# 2013_Carte_Factorisee.net
KiCad netlist of a schematic drawn in Altium Designer
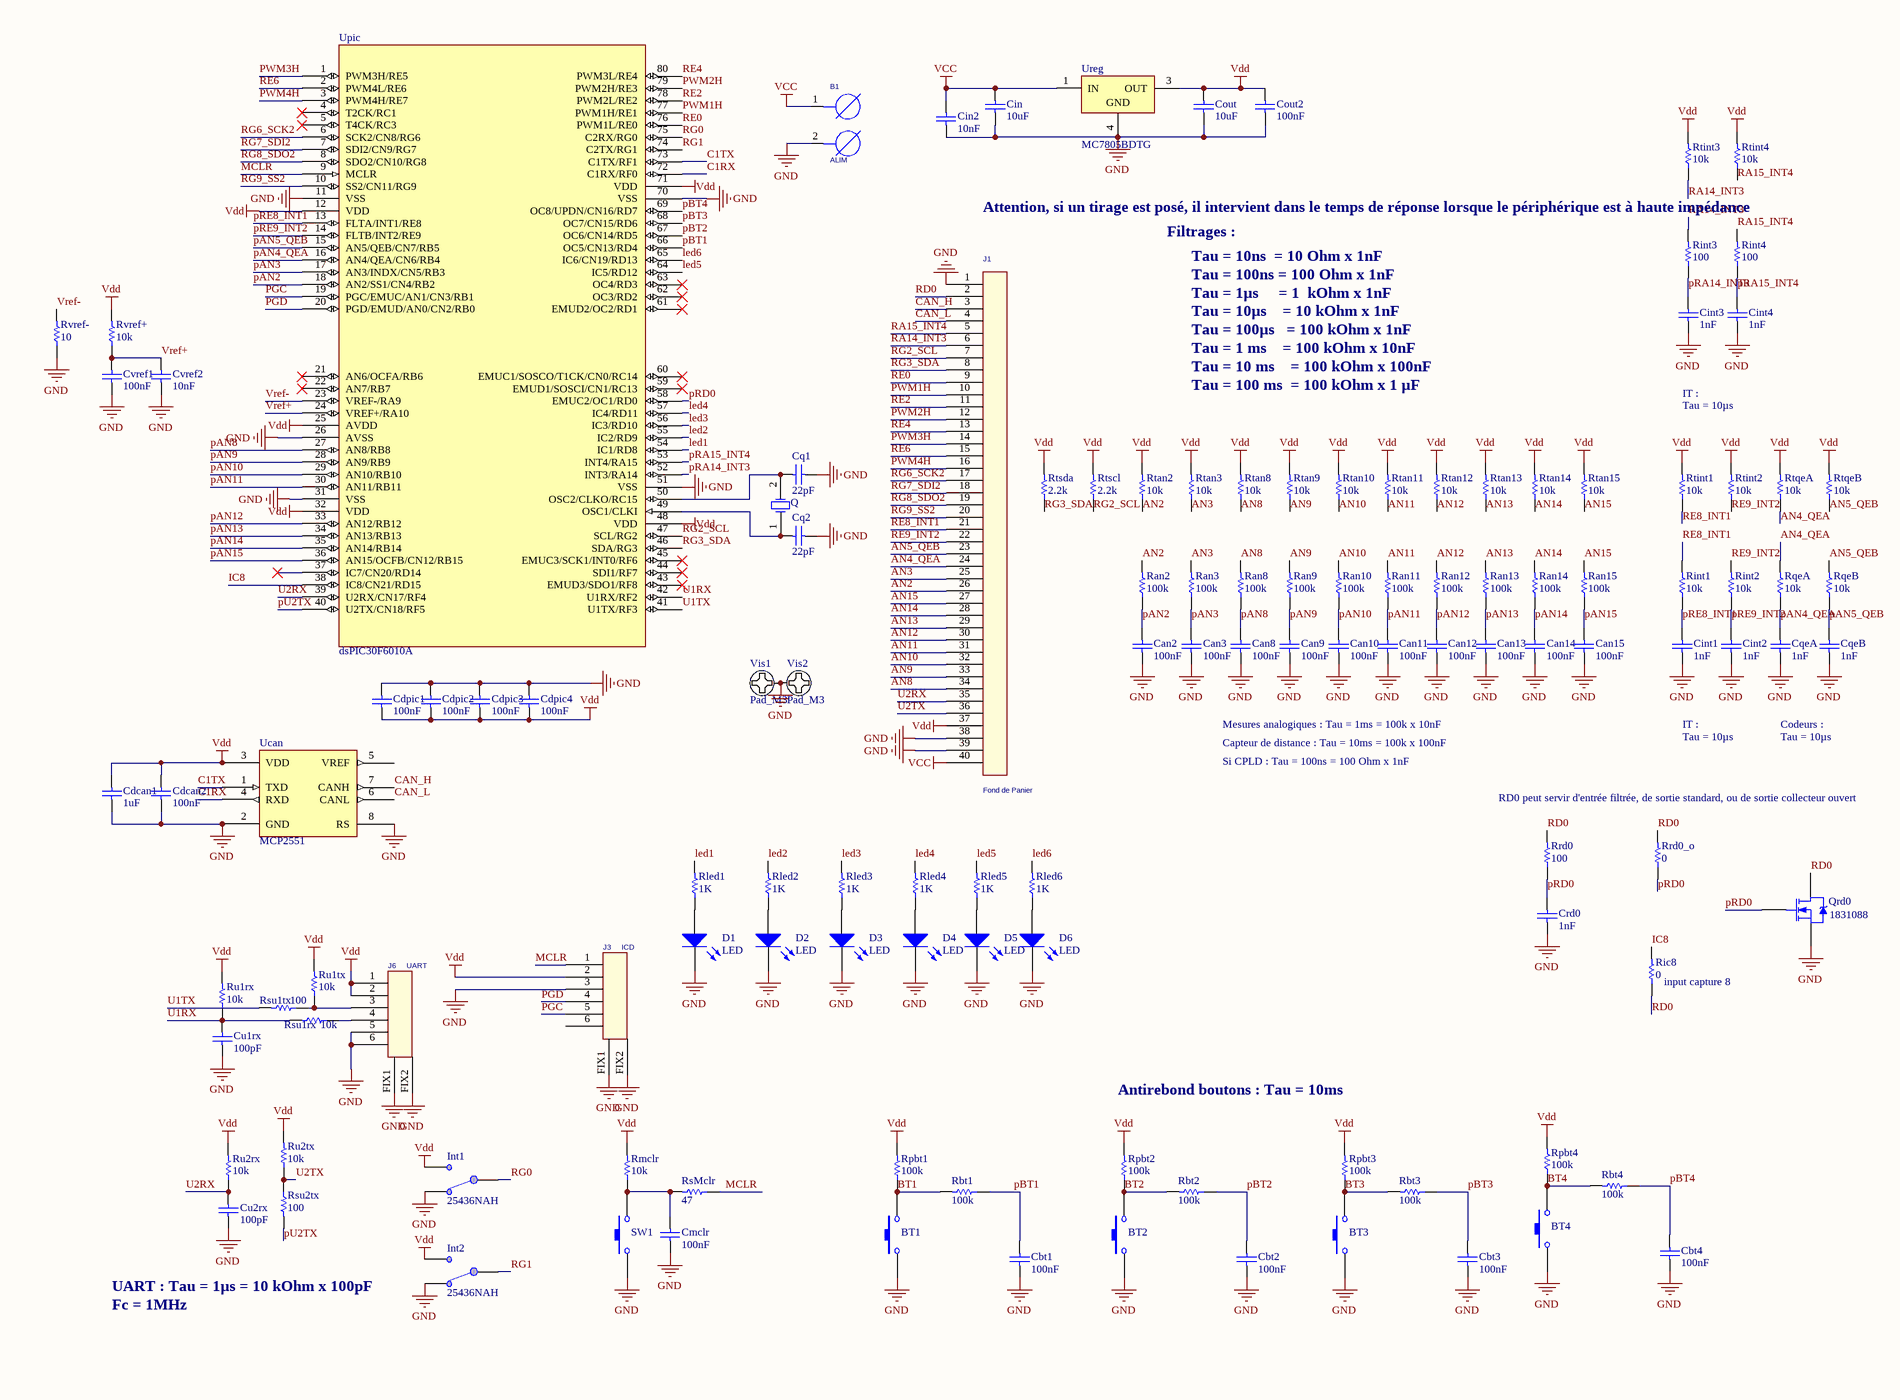
[diagram p0: 2013_Carte_Factorisee.SchDoc, left]
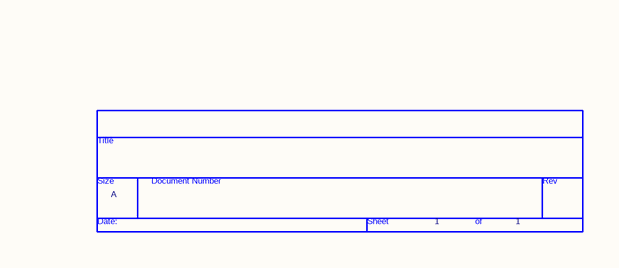
[diagram p1: 2013_Carte_Factorisee.SchDoc, right]

(export (version "E")
  (design (tool "Eeschema 10.0.6"))
  (components
    (comp (ref "*")
      (value "TitleBlock0")
      (fields (field (name "PAGE COUNT") "1") (field (name "PAGE NUMBER") "1") (field (name "PAGE SIZE") "A"))
      (libsource (lib "*") (part "TitleBlock0"))
    )
    (comp (ref "B1") (value "ALIM") (footprint "BORNIER2") (libsource (lib "*") (part "BORNIER2")))
    (comp (ref "BT1")
      (value "SW_Pushbutton_6x6mm_Vertical")
      (footprint "Switch 6x6 Vertical")
      (description "Switch tactil 6mm x 6mm Vertical")
      (fields (field (name "PUBLISHER") "Damien Guitton"))
      (libsource (lib "DG_Interrupteur") (part "SW_Pushbutton_6x6mm_Vertical"))
    )
    (comp (ref "BT2")
      (value "SW_Pushbutton_6x6mm_Vertical")
      (footprint "Switch 6x6 Vertical")
      (description "Switch tactil 6mm x 6mm Vertical")
      (fields (field (name "PUBLISHER") "Damien Guitton"))
      (libsource (lib "DG_Interrupteur") (part "SW_Pushbutton_6x6mm_Vertical"))
    )
    (comp (ref "BT3")
      (value "SW_Pushbutton_6x6mm_Vertical")
      (footprint "Switch 6x6 Vertical")
      (description "Switch tactil 6mm x 6mm Vertical")
      (fields (field (name "PUBLISHER") "Damien Guitton"))
      (libsource (lib "DG_Interrupteur") (part "SW_Pushbutton_6x6mm_Vertical"))
    )
    (comp (ref "BT4")
      (value "SW_Pushbutton_6x6mm_Vertical")
      (footprint "Switch 6x6 Vertical")
      (description "Switch tactil 6mm x 6mm Vertical")
      (fields (field (name "PUBLISHER") "Damien Guitton"))
      (libsource (lib "DG_Interrupteur") (part "SW_Pushbutton_6x6mm_Vertical"))
    )
    (comp (ref "Can2")
      (value "100nF")
      (footprint "C0805_N")
      (description "Capacitor")
      (fields (field (name "PUBLISHER") "Altium Limited"))
      (libsource (lib "DG_Condensateur") (part "Capacitor"))
    )
    (comp (ref "Can3")
      (value "100nF")
      (footprint "C0805_N")
      (description "Capacitor")
      (fields (field (name "PUBLISHER") "Altium Limited"))
      (libsource (lib "DG_Condensateur") (part "Capacitor"))
    )
    (comp (ref "Can8")
      (value "100nF")
      (footprint "C0805_N")
      (description "Capacitor")
      (fields (field (name "PUBLISHER") "Altium Limited"))
      (libsource (lib "DG_Condensateur") (part "Capacitor"))
    )
    (comp (ref "Can9")
      (value "100nF")
      (footprint "C0805_N")
      (description "Capacitor")
      (fields (field (name "PUBLISHER") "Altium Limited"))
      (libsource (lib "DG_Condensateur") (part "Capacitor"))
    )
    (comp (ref "Can10")
      (value "100nF")
      (footprint "C0805_N")
      (description "Capacitor")
      (fields (field (name "PUBLISHER") "Altium Limited"))
      (libsource (lib "DG_Condensateur") (part "Capacitor"))
    )
    (comp (ref "Can11")
      (value "100nF")
      (footprint "C0805_N")
      (description "Capacitor")
      (fields (field (name "PUBLISHER") "Altium Limited"))
      (libsource (lib "DG_Condensateur") (part "Capacitor"))
    )
    (comp (ref "Can12")
      (value "100nF")
      (footprint "C0805_N")
      (description "Capacitor")
      (fields (field (name "PUBLISHER") "Altium Limited"))
      (libsource (lib "DG_Condensateur") (part "Capacitor"))
    )
    (comp (ref "Can13")
      (value "100nF")
      (footprint "C0805_N")
      (description "Capacitor")
      (fields (field (name "PUBLISHER") "Altium Limited"))
      (libsource (lib "DG_Condensateur") (part "Capacitor"))
    )
    (comp (ref "Can14")
      (value "100nF")
      (footprint "C0805_N")
      (description "Capacitor")
      (fields (field (name "PUBLISHER") "Altium Limited"))
      (libsource (lib "DG_Condensateur") (part "Capacitor"))
    )
    (comp (ref "Can15")
      (value "100nF")
      (footprint "C0805_N")
      (description "Capacitor")
      (fields (field (name "PUBLISHER") "Altium Limited"))
      (libsource (lib "DG_Condensateur") (part "Capacitor"))
    )
    (comp (ref "Cbt1")
      (value "100nF")
      (footprint "C0805_N")
      (description "Capacitor")
      (fields (field (name "PUBLISHER") "Altium Limited"))
      (libsource (lib "DG_Condensateur") (part "Capacitor"))
    )
    (comp (ref "Cbt2")
      (value "100nF")
      (footprint "C0805_N")
      (description "Capacitor")
      (fields (field (name "PUBLISHER") "Altium Limited"))
      (libsource (lib "DG_Condensateur") (part "Capacitor"))
    )
    (comp (ref "Cbt3")
      (value "100nF")
      (footprint "C0805_N")
      (description "Capacitor")
      (fields (field (name "PUBLISHER") "Altium Limited"))
      (libsource (lib "DG_Condensateur") (part "Capacitor"))
    )
    (comp (ref "Cbt4")
      (value "100nF")
      (footprint "C0805_N")
      (description "Capacitor")
      (fields (field (name "PUBLISHER") "Altium Limited"))
      (libsource (lib "DG_Condensateur") (part "Capacitor"))
    )
    (comp (ref "Cdcan1")
      (value "1uF")
      (footprint "C1206_N")
      (description "Capacitor")
      (fields (field (name "PUBLISHER") "Altium Limited"))
      (libsource (lib "DG_Condensateur") (part "Capacitor"))
    )
    (comp (ref "Cdcan2")
      (value "100nF")
      (footprint "C0805_N")
      (description "Capacitor")
      (fields (field (name "PUBLISHER") "Altium Limited"))
      (libsource (lib "DG_Condensateur") (part "Capacitor"))
    )
    (comp (ref "Cdpic1")
      (value "100nF")
      (footprint "C0805_N")
      (description "Capacitor")
      (fields (field (name "PUBLISHER") "Altium Limited"))
      (libsource (lib "DG_Condensateur") (part "Capacitor"))
    )
    (comp (ref "Cdpic2")
      (value "100nF")
      (footprint "C0805_N")
      (description "Capacitor")
      (fields (field (name "PUBLISHER") "Altium Limited"))
      (libsource (lib "DG_Condensateur") (part "Capacitor"))
    )
    (comp (ref "Cdpic3")
      (value "100nF")
      (footprint "C0805_N")
      (description "Capacitor")
      (fields (field (name "PUBLISHER") "Altium Limited"))
      (libsource (lib "DG_Condensateur") (part "Capacitor"))
    )
    (comp (ref "Cdpic4")
      (value "100nF")
      (footprint "C0805_N")
      (description "Capacitor")
      (fields (field (name "PUBLISHER") "Altium Limited"))
      (libsource (lib "DG_Condensateur") (part "Capacitor"))
    )
    (comp (ref "Cin")
      (value "10uF")
      (footprint "C1206_N")
      (description "Capacitor")
      (fields (field (name "PUBLISHER") "Altium Limited"))
      (libsource (lib "DG_Condensateur") (part "Capacitor"))
    )
    (comp (ref "Cin2")
      (value "10nF")
      (footprint "C0805_N")
      (description "Capacitor")
      (fields (field (name "PUBLISHER") "Altium Limited"))
      (libsource (lib "DG_Condensateur") (part "Capacitor"))
    )
    (comp (ref "Cint1")
      (value "1nF")
      (footprint "C0805_N")
      (description "Capacitor")
      (fields (field (name "PUBLISHER") "Altium Limited"))
      (libsource (lib "DG_Condensateur") (part "Capacitor"))
    )
    (comp (ref "Cint2")
      (value "1nF")
      (footprint "C0805_N")
      (description "Capacitor")
      (fields (field (name "PUBLISHER") "Altium Limited"))
      (libsource (lib "DG_Condensateur") (part "Capacitor"))
    )
    (comp (ref "Cint3")
      (value "1nF")
      (footprint "C0805_N")
      (description "Capacitor")
      (fields (field (name "PUBLISHER") "Altium Limited"))
      (libsource (lib "DG_Condensateur") (part "Capacitor"))
    )
    (comp (ref "Cint4")
      (value "1nF")
      (footprint "C0805_N")
      (description "Capacitor")
      (fields (field (name "PUBLISHER") "Altium Limited"))
      (libsource (lib "DG_Condensateur") (part "Capacitor"))
    )
    (comp (ref "Cmclr")
      (value "100nF")
      (footprint "C0805_N")
      (description "Capacitor")
      (fields (field (name "PUBLISHER") "Altium Limited"))
      (libsource (lib "DG_Condensateur") (part "Capacitor"))
    )
    (comp (ref "Cout")
      (value "10uF")
      (footprint "C1206_N")
      (description "Capacitor")
      (fields (field (name "PUBLISHER") "Altium Limited"))
      (libsource (lib "DG_Condensateur") (part "Capacitor"))
    )
    (comp (ref "Cout2")
      (value "100nF")
      (footprint "C0805_N")
      (description "Capacitor")
      (fields (field (name "PUBLISHER") "Altium Limited"))
      (libsource (lib "DG_Condensateur") (part "Capacitor"))
    )
    (comp (ref "Cq1")
      (value "22pF")
      (footprint "C0805_N")
      (description "Capacitor")
      (fields (field (name "PUBLISHER") "Altium Limited"))
      (libsource (lib "DG_Condensateur") (part "Capacitor"))
    )
    (comp (ref "Cq2")
      (value "22pF")
      (footprint "C0805_N")
      (description "Capacitor")
      (fields (field (name "PUBLISHER") "Altium Limited"))
      (libsource (lib "DG_Condensateur") (part "Capacitor"))
    )
    (comp (ref "CqeA")
      (value "1nF")
      (footprint "C0805_N")
      (description "Capacitor")
      (fields (field (name "PUBLISHER") "Altium Limited"))
      (libsource (lib "DG_Condensateur") (part "Capacitor"))
    )
    (comp (ref "CqeB")
      (value "1nF")
      (footprint "C0805_N")
      (description "Capacitor")
      (fields (field (name "PUBLISHER") "Altium Limited"))
      (libsource (lib "DG_Condensateur") (part "Capacitor"))
    )
    (comp (ref "Crd0")
      (value "1nF")
      (footprint "C0805_N")
      (description "Capacitor")
      (fields (field (name "PUBLISHER") "Altium Limited"))
      (libsource (lib "DG_Condensateur") (part "Capacitor"))
    )
    (comp (ref "Cu1rx")
      (value "100pF")
      (footprint "C0805_N")
      (description "Capacitor")
      (fields (field (name "PUBLISHER") "Altium Limited"))
      (libsource (lib "DG_Condensateur") (part "Capacitor"))
    )
    (comp (ref "Cu2rx")
      (value "100pF")
      (footprint "C0805_N")
      (description "Capacitor")
      (fields (field (name "PUBLISHER") "Altium Limited"))
      (libsource (lib "DG_Condensateur") (part "Capacitor"))
    )
    (comp (ref "Cvref1")
      (value "100nF")
      (footprint "C0805_N")
      (description "Capacitor")
      (fields (field (name "PUBLISHER") "Altium Limited"))
      (libsource (lib "DG_Condensateur") (part "Capacitor"))
    )
    (comp (ref "Cvref2")
      (value "10nF")
      (footprint "C0805_N")
      (description "Capacitor")
      (fields (field (name "PUBLISHER") "Altium Limited"))
      (libsource (lib "DG_Condensateur") (part "Capacitor"))
    )
    (comp (ref "D1")
      (value "LED")
      (footprint "LED_3mm")
      (description "Typical LED")
      (fields (field (name "PUBLISHER") "Altium Limited"))
      (libsource (lib "DG_LED") (part "LED"))
    )
    (comp (ref "D2")
      (value "LED")
      (footprint "LED_3mm")
      (description "Typical LED")
      (fields (field (name "PUBLISHER") "Altium Limited"))
      (libsource (lib "DG_LED") (part "LED"))
    )
    (comp (ref "D3")
      (value "LED")
      (footprint "LED_3mm")
      (description "Typical LED")
      (fields (field (name "PUBLISHER") "Altium Limited"))
      (libsource (lib "DG_LED") (part "LED"))
    )
    (comp (ref "D4")
      (value "LED")
      (footprint "LED_3mm")
      (description "Typical LED")
      (fields (field (name "PUBLISHER") "Altium Limited"))
      (libsource (lib "DG_LED") (part "LED"))
    )
    (comp (ref "D5")
      (value "LED")
      (footprint "LED_3mm")
      (description "Typical LED")
      (fields (field (name "PUBLISHER") "Altium Limited"))
      (libsource (lib "DG_LED") (part "LED"))
    )
    (comp (ref "D6")
      (value "LED")
      (footprint "LED_3mm")
      (description "Typical LED")
      (fields (field (name "PUBLISHER") "Altium Limited"))
      (libsource (lib "DG_LED") (part "LED"))
    )
    (comp (ref "Int1")
      (value "25436NAH")
      (footprint "SW_UNIPOL_DROIT - APEM 523X B")
      (description "Switch unipolaire a levier")
      (libsource (lib "DG_Interrupteur") (part "SW SPDT- APEM Série 523x"))
    )
    (comp (ref "Int2")
      (value "25436NAH")
      (footprint "SW_UNIPOL_DROIT - APEM 523X B")
      (description "Switch unipolaire a levier")
      (libsource (lib "DG_Interrupteur") (part "SW SPDT- APEM Série 523x"))
    )
    (comp (ref "J1")
      (value "Fond de Panier")
      (footprint "HE10/40_FACTO")
      (libsource (lib "*") (part "CONNECTEUR_HE10_40"))
    )
    (comp (ref "J3") (value "ICD") (footprint "RJ11_6/6") (libsource (lib "*") (part "CONNECTEUR_RJ12")))
    (comp (ref "J6") (value "UART") (footprint "RJ11_6/6") (libsource (lib "*") (part "CONNECTEUR_RJ12")))
    (comp (ref "Q")
      (value "QU")
      (footprint "QUARTZ_DROIT_BP")
      (description "Crystal Oscillator")
      (fields (field (name "PUBLISHER") "Altium Limited"))
      (libsource (lib "miniprojet") (part "QUARTZ_DROIT_BAS_PROFIL"))
    )
    (comp (ref "Qrd0")
      (value "~")
      (footprint "SOT23")
      (description "MOSFET N")
      (fields (field (name "FAR") "1831088"))
      (libsource (lib "DG_Transistor") (part "FDP100N10"))
    )
    (comp (ref "Ran2")
      (value "100k")
      (footprint "R1206_N")
      (description "Resistor")
      (fields (field (name "PUBLISHER") "Altium Limited"))
      (libsource (lib "DG_Resistance") (part "Resistor"))
    )
    (comp (ref "Ran3")
      (value "100k")
      (footprint "R1206_N")
      (description "Resistor")
      (fields (field (name "PUBLISHER") "Altium Limited"))
      (libsource (lib "DG_Resistance") (part "Resistor"))
    )
    (comp (ref "Ran8")
      (value "100k")
      (footprint "R1206_N")
      (description "Resistor")
      (fields (field (name "PUBLISHER") "Altium Limited"))
      (libsource (lib "DG_Resistance") (part "Resistor"))
    )
    (comp (ref "Ran9")
      (value "100k")
      (footprint "R1206_N")
      (description "Resistor")
      (fields (field (name "PUBLISHER") "Altium Limited"))
      (libsource (lib "DG_Resistance") (part "Resistor"))
    )
    (comp (ref "Ran10")
      (value "100k")
      (footprint "R1206_N")
      (description "Resistor")
      (fields (field (name "PUBLISHER") "Altium Limited"))
      (libsource (lib "DG_Resistance") (part "Resistor"))
    )
    (comp (ref "Ran11")
      (value "100k")
      (footprint "R1206_N")
      (description "Resistor")
      (fields (field (name "PUBLISHER") "Altium Limited"))
      (libsource (lib "DG_Resistance") (part "Resistor"))
    )
    (comp (ref "Ran12")
      (value "100k")
      (footprint "R1206_N")
      (description "Resistor")
      (fields (field (name "PUBLISHER") "Altium Limited"))
      (libsource (lib "DG_Resistance") (part "Resistor"))
    )
    (comp (ref "Ran13")
      (value "100k")
      (footprint "R1206_N")
      (description "Resistor")
      (fields (field (name "PUBLISHER") "Altium Limited"))
      (libsource (lib "DG_Resistance") (part "Resistor"))
    )
    (comp (ref "Ran14")
      (value "100k")
      (footprint "R1206_N")
      (description "Resistor")
      (fields (field (name "PUBLISHER") "Altium Limited"))
      (libsource (lib "DG_Resistance") (part "Resistor"))
    )
    (comp (ref "Ran15")
      (value "100k")
      (footprint "R1206_N")
      (description "Resistor")
      (fields (field (name "PUBLISHER") "Altium Limited"))
      (libsource (lib "DG_Resistance") (part "Resistor"))
    )
    (comp (ref "Rbt1")
      (value "100k")
      (footprint "R1206_N")
      (description "Resistor")
      (fields (field (name "PUBLISHER") "Altium Limited"))
      (libsource (lib "DG_Resistance") (part "Resistor"))
    )
    (comp (ref "Rbt2")
      (value "100k")
      (footprint "R1206_N")
      (description "Resistor")
      (fields (field (name "PUBLISHER") "Altium Limited"))
      (libsource (lib "DG_Resistance") (part "Resistor"))
    )
    (comp (ref "Rbt3")
      (value "100k")
      (footprint "R1206_N")
      (description "Resistor")
      (fields (field (name "PUBLISHER") "Altium Limited"))
      (libsource (lib "DG_Resistance") (part "Resistor"))
    )
    (comp (ref "Rbt4")
      (value "100k")
      (footprint "R1206_N")
      (description "Resistor")
      (fields (field (name "PUBLISHER") "Altium Limited"))
      (libsource (lib "DG_Resistance") (part "Resistor"))
    )
    (comp (ref "Ric8")
      (value "0")
      (footprint "R1206_N")
      (description "Resistor")
      (fields (field (name "PUBLISHER") "Altium Limited"))
      (libsource (lib "DG_Resistance") (part "Resistor"))
    )
    (comp (ref "Rint1")
      (value "10k")
      (footprint "R1206_N")
      (description "Resistor")
      (fields (field (name "PUBLISHER") "Altium Limited"))
      (libsource (lib "DG_Resistance") (part "Resistor"))
    )
    (comp (ref "Rint2")
      (value "10k")
      (footprint "R1206_N")
      (description "Resistor")
      (fields (field (name "PUBLISHER") "Altium Limited"))
      (libsource (lib "DG_Resistance") (part "Resistor"))
    )
    (comp (ref "Rint3")
      (value "100")
      (footprint "R1206_N")
      (description "Resistor")
      (fields (field (name "PUBLISHER") "Altium Limited"))
      (libsource (lib "DG_Resistance") (part "Resistor"))
    )
    (comp (ref "Rint4")
      (value "100")
      (footprint "R1206_N")
      (description "Resistor")
      (fields (field (name "PUBLISHER") "Altium Limited"))
      (libsource (lib "DG_Resistance") (part "Resistor"))
    )
    (comp (ref "Rled1")
      (value "1K")
      (footprint "R1206_N")
      (description "Resistor")
      (fields (field (name "PUBLISHER") "Altium Limited"))
      (libsource (lib "DG_Resistance") (part "Resistor"))
    )
    (comp (ref "Rled2")
      (value "1K")
      (footprint "R1206_N")
      (description "Resistor")
      (fields (field (name "PUBLISHER") "Altium Limited"))
      (libsource (lib "DG_Resistance") (part "Resistor"))
    )
    (comp (ref "Rled3")
      (value "1K")
      (footprint "R1206_N")
      (description "Resistor")
      (fields (field (name "PUBLISHER") "Altium Limited"))
      (libsource (lib "DG_Resistance") (part "Resistor"))
    )
    (comp (ref "Rled4")
      (value "1K")
      (footprint "R1206_N")
      (description "Resistor")
      (fields (field (name "PUBLISHER") "Altium Limited"))
      (libsource (lib "DG_Resistance") (part "Resistor"))
    )
    (comp (ref "Rled5")
      (value "1K")
      (footprint "R1206_N")
      (description "Resistor")
      (fields (field (name "PUBLISHER") "Altium Limited"))
      (libsource (lib "DG_Resistance") (part "Resistor"))
    )
    (comp (ref "Rled6")
      (value "1K")
      (footprint "R1206_N")
      (description "Resistor")
      (fields (field (name "PUBLISHER") "Altium Limited"))
      (libsource (lib "DG_Resistance") (part "Resistor"))
    )
    (comp (ref "Rmclr")
      (value "10k")
      (footprint "R1206_N")
      (description "Resistor")
      (fields (field (name "PUBLISHER") "Altium Limited"))
      (libsource (lib "DG_Resistance") (part "Resistor"))
    )
    (comp (ref "Rpbt1")
      (value "100k")
      (footprint "R1206_N")
      (description "Resistor")
      (fields (field (name "PUBLISHER") "Altium Limited"))
      (libsource (lib "DG_Resistance") (part "Resistor"))
    )
    (comp (ref "Rpbt2")
      (value "100k")
      (footprint "R1206_N")
      (description "Resistor")
      (fields (field (name "PUBLISHER") "Altium Limited"))
      (libsource (lib "DG_Resistance") (part "Resistor"))
    )
    (comp (ref "Rpbt3")
      (value "100k")
      (footprint "R1206_N")
      (description "Resistor")
      (fields (field (name "PUBLISHER") "Altium Limited"))
      (libsource (lib "DG_Resistance") (part "Resistor"))
    )
    (comp (ref "Rpbt4")
      (value "100k")
      (footprint "R1206_N")
      (description "Resistor")
      (fields (field (name "PUBLISHER") "Altium Limited"))
      (libsource (lib "DG_Resistance") (part "Resistor"))
    )
    (comp (ref "RqeA")
      (value "10k")
      (footprint "R1206_N")
      (description "Resistor")
      (fields (field (name "PUBLISHER") "Altium Limited"))
      (libsource (lib "DG_Resistance") (part "Resistor"))
    )
    (comp (ref "RqeB")
      (value "10k")
      (footprint "R1206_N")
      (description "Resistor")
      (fields (field (name "PUBLISHER") "Altium Limited"))
      (libsource (lib "DG_Resistance") (part "Resistor"))
    )
    (comp (ref "Rrd0")
      (value "100")
      (footprint "R1206_N")
      (description "Resistor")
      (fields (field (name "PUBLISHER") "Altium Limited"))
      (libsource (lib "DG_Resistance") (part "Resistor"))
    )
    (comp (ref "Rrd0_o")
      (value "0")
      (footprint "R1206_N")
      (description "Resistor")
      (fields (field (name "PUBLISHER") "Altium Limited"))
      (libsource (lib "DG_Resistance") (part "Resistor"))
    )
    (comp (ref "RsMclr")
      (value "47")
      (footprint "R1206_N")
      (description "Resistor")
      (fields (field (name "PUBLISHER") "Altium Limited"))
      (libsource (lib "DG_Resistance") (part "Resistor"))
    )
    (comp (ref "Rsu1rx")
      (value "10k")
      (footprint "R1206_N")
      (description "Resistor")
      (fields (field (name "PUBLISHER") "Altium Limited"))
      (libsource (lib "DG_Resistance") (part "Resistor"))
    )
    (comp (ref "Rsu1tx")
      (value "100")
      (footprint "R1206_N")
      (description "Resistor")
      (fields (field (name "PUBLISHER") "Altium Limited"))
      (libsource (lib "DG_Resistance") (part "Resistor"))
    )
    (comp (ref "Rsu2tx")
      (value "100")
      (footprint "R1206_N")
      (description "Resistor")
      (fields (field (name "PUBLISHER") "Altium Limited"))
      (libsource (lib "DG_Resistance") (part "Resistor"))
    )
    (comp (ref "Rtan2")
      (value "10k")
      (footprint "R1206_N")
      (description "Resistor")
      (fields (field (name "PUBLISHER") "Altium Limited"))
      (libsource (lib "DG_Resistance") (part "Resistor"))
    )
    (comp (ref "Rtan3")
      (value "10k")
      (footprint "R1206_N")
      (description "Resistor")
      (fields (field (name "PUBLISHER") "Altium Limited"))
      (libsource (lib "DG_Resistance") (part "Resistor"))
    )
    (comp (ref "Rtan8")
      (value "10k")
      (footprint "R1206_N")
      (description "Resistor")
      (fields (field (name "PUBLISHER") "Altium Limited"))
      (libsource (lib "DG_Resistance") (part "Resistor"))
    )
    (comp (ref "Rtan9")
      (value "10k")
      (footprint "R1206_N")
      (description "Resistor")
      (fields (field (name "PUBLISHER") "Altium Limited"))
      (libsource (lib "DG_Resistance") (part "Resistor"))
    )
    (comp (ref "Rtan10")
      (value "10k")
      (footprint "R1206_N")
      (description "Resistor")
      (fields (field (name "PUBLISHER") "Altium Limited"))
      (libsource (lib "DG_Resistance") (part "Resistor"))
    )
    (comp (ref "Rtan11")
      (value "10k")
      (footprint "R1206_N")
      (description "Resistor")
      (fields (field (name "PUBLISHER") "Altium Limited"))
      (libsource (lib "DG_Resistance") (part "Resistor"))
    )
    (comp (ref "Rtan12")
      (value "10k")
      (footprint "R1206_N")
      (description "Resistor")
      (fields (field (name "PUBLISHER") "Altium Limited"))
      (libsource (lib "DG_Resistance") (part "Resistor"))
    )
    (comp (ref "Rtan13")
      (value "10k")
      (footprint "R1206_N")
      (description "Resistor")
      (fields (field (name "PUBLISHER") "Altium Limited"))
      (libsource (lib "DG_Resistance") (part "Resistor"))
    )
    (comp (ref "Rtan14")
      (value "10k")
      (footprint "R1206_N")
      (description "Resistor")
      (fields (field (name "PUBLISHER") "Altium Limited"))
      (libsource (lib "DG_Resistance") (part "Resistor"))
    )
    (comp (ref "Rtan15")
      (value "10k")
      (footprint "R1206_N")
      (description "Resistor")
      (fields (field (name "PUBLISHER") "Altium Limited"))
      (libsource (lib "DG_Resistance") (part "Resistor"))
    )
    (comp (ref "Rtint1")
      (value "10k")
      (footprint "R1206_N")
      (description "Resistor")
      (fields (field (name "PUBLISHER") "Altium Limited"))
      (libsource (lib "DG_Resistance") (part "Resistor"))
    )
    (comp (ref "Rtint2")
      (value "10k")
      (footprint "R1206_N")
      (description "Resistor")
      (fields (field (name "PUBLISHER") "Altium Limited"))
      (libsource (lib "DG_Resistance") (part "Resistor"))
    )
    (comp (ref "Rtint3")
      (value "10k")
      (footprint "R1206_N")
      (description "Resistor")
      (fields (field (name "PUBLISHER") "Altium Limited"))
      (libsource (lib "DG_Resistance") (part "Resistor"))
    )
    (comp (ref "Rtint4")
      (value "10k")
      (footprint "R1206_N")
      (description "Resistor")
      (fields (field (name "PUBLISHER") "Altium Limited"))
      (libsource (lib "DG_Resistance") (part "Resistor"))
    )
    (comp (ref "RtqeA")
      (value "10k")
      (footprint "R1206_N")
      (description "Resistor")
      (fields (field (name "PUBLISHER") "Altium Limited"))
      (libsource (lib "DG_Resistance") (part "Resistor"))
    )
    (comp (ref "RtqeB")
      (value "10k")
      (footprint "R1206_N")
      (description "Resistor")
      (fields (field (name "PUBLISHER") "Altium Limited"))
      (libsource (lib "DG_Resistance") (part "Resistor"))
    )
    (comp (ref "Rtscl")
      (value "2.2k")
      (footprint "R1206_N")
      (description "Resistor")
      (fields (field (name "PUBLISHER") "Altium Limited"))
      (libsource (lib "DG_Resistance") (part "Resistor"))
    )
    (comp (ref "Rtsda")
      (value "2.2k")
      (footprint "R1206_N")
      (description "Resistor")
      (fields (field (name "PUBLISHER") "Altium Limited"))
      (libsource (lib "DG_Resistance") (part "Resistor"))
    )
    (comp (ref "Ru1rx")
      (value "10k")
      (footprint "R1206_N")
      (description "Resistor")
      (fields (field (name "PUBLISHER") "Altium Limited"))
      (libsource (lib "DG_Resistance") (part "Resistor"))
    )
    (comp (ref "Ru1tx")
      (value "10k")
      (footprint "R1206_N")
      (description "Resistor")
      (fields (field (name "PUBLISHER") "Altium Limited"))
      (libsource (lib "DG_Resistance") (part "Resistor"))
    )
    (comp (ref "Ru2rx")
      (value "10k")
      (footprint "R1206_N")
      (description "Resistor")
      (fields (field (name "PUBLISHER") "Altium Limited"))
      (libsource (lib "DG_Resistance") (part "Resistor"))
    )
    (comp (ref "Ru2tx")
      (value "10k")
      (footprint "R1206_N")
      (description "Resistor")
      (fields (field (name "PUBLISHER") "Altium Limited"))
      (libsource (lib "DG_Resistance") (part "Resistor"))
    )
    (comp (ref "Rvref+")
      (value "10k")
      (footprint "R1206_N")
      (description "Resistor")
      (fields (field (name "PUBLISHER") "Altium Limited"))
      (libsource (lib "DG_Resistance") (part "Resistor"))
    )
    (comp (ref "Rvref-")
      (value "10")
      (footprint "R1206_N")
      (description "Resistor")
      (fields (field (name "PUBLISHER") "Altium Limited"))
      (libsource (lib "DG_Resistance") (part "Resistor"))
    )
    (comp (ref "SW1")
      (value "SW_Pushbutton_6x6mm_Vertical")
      (footprint "Switch 6x6 Vertical")
      (description "Switch tactil 6mm x 6mm Vertical")
      (fields (field (name "PUBLISHER") "Damien Guitton"))
      (libsource (lib "DG_Interrupteur") (part "SW_Pushbutton_6x6mm_Vertical"))
    )
    (comp (ref "Ucan")
      (value "MCP2551")
      (footprint "SOIC150-8_N")
      (description "High Speed Can Transceiver")
      (fields (field (name "PUBLISHER") "Altium Limited"))
      (libsource (lib "Microchip Interface Line Transceiver") (part "MCP2551"))
    )
    (comp (ref "Upic")
      (value "dsPIC30F6010A")
      (footprint "TQFP80_N")
      (description "High-Performance, 16-bit Digital Signal Controllers")
      (libsource (lib "DG_Microcontroleur") (part "dsPIC30F6010A"))
    )
    (comp (ref "Ureg")
      (value "MC7805BDTG")
      (footprint "369A-13")
      (description "Three-Terminal Positive Voltage Regulator")
      (fields (field (name "PUBLISHER") "Altium Limited"))
      (libsource (lib "ON Semi Power Mgt Voltage Regulator") (part "MC7805ACD2T"))
    )
    (comp (ref "Vis1")
      (value "Pad_M3")
      (footprint "M3x6mm")
      (description "Vis M3 X 6mm _TORX_Tête 6mm")
      (fields (field (name "PUBLISHER") "Damien Guitton"))
      (libsource (lib "DG_Mecanique") (part "Vis M3 X 6mm _TORX_Tête 6mm"))
    )
    (comp (ref "Vis2")
      (value "Pad_M3")
      (footprint "M3x6mm")
      (description "Vis M3 X 6mm _TORX_Tête 6mm")
      (fields (field (name "PUBLISHER") "Damien Guitton"))
      (libsource (lib "DG_Mecanique") (part "Vis M3 X 6mm _TORX_Tête 6mm"))
    )
  )
  (nets
    (net (code "1") (name "/AN2") (class "Default")
      (node (ref "J1") (pin "26") (pinfunction "26_26") (pintype "passive"))
      (node (ref "Ran2") (pin "2") (pinfunction "2_2") (pintype "passive"))
      (node (ref "Rtan2") (pin "1") (pinfunction "1_1") (pintype "passive"))
    )
    (net (code "2") (name "/AN3") (class "Default")
      (node (ref "J1") (pin "25") (pinfunction "25_25") (pintype "passive"))
      (node (ref "Ran3") (pin "2") (pinfunction "2_2") (pintype "passive"))
      (node (ref "Rtan3") (pin "1") (pinfunction "1_1") (pintype "passive"))
    )
    (net (code "3") (name "/AN4_QEA") (class "Default")
      (node (ref "J1") (pin "24") (pinfunction "24_24") (pintype "passive"))
      (node (ref "RqeA") (pin "2") (pinfunction "2_2") (pintype "passive"))
      (node (ref "RtqeA") (pin "1") (pinfunction "1_1") (pintype "passive"))
    )
    (net (code "4") (name "/AN5_QEB") (class "Default")
      (node (ref "J1") (pin "23") (pinfunction "23_23") (pintype "passive"))
      (node (ref "RqeB") (pin "2") (pinfunction "2_2") (pintype "passive"))
      (node (ref "RtqeB") (pin "1") (pinfunction "1_1") (pintype "passive"))
    )
    (net (code "5") (name "/AN8") (class "Default")
      (node (ref "J1") (pin "34") (pinfunction "34_34") (pintype "passive"))
      (node (ref "Ran8") (pin "2") (pinfunction "2_2") (pintype "passive"))
      (node (ref "Rtan8") (pin "1") (pinfunction "1_1") (pintype "passive"))
    )
    (net (code "6") (name "/AN9") (class "Default")
      (node (ref "J1") (pin "33") (pinfunction "33_33") (pintype "passive"))
      (node (ref "Ran9") (pin "2") (pinfunction "2_2") (pintype "passive"))
      (node (ref "Rtan9") (pin "1") (pinfunction "1_1") (pintype "passive"))
    )
    (net (code "7") (name "/AN10") (class "Default")
      (node (ref "J1") (pin "32") (pinfunction "32_32") (pintype "passive"))
      (node (ref "Ran10") (pin "2") (pinfunction "2_2") (pintype "passive"))
      (node (ref "Rtan10") (pin "1") (pinfunction "1_1") (pintype "passive"))
    )
    (net (code "8") (name "/AN11") (class "Default")
      (node (ref "J1") (pin "31") (pinfunction "31_31") (pintype "passive"))
      (node (ref "Ran11") (pin "2") (pinfunction "2_2") (pintype "passive"))
      (node (ref "Rtan11") (pin "1") (pinfunction "1_1") (pintype "passive"))
    )
    (net (code "9") (name "/AN12") (class "Default")
      (node (ref "J1") (pin "30") (pinfunction "30_30") (pintype "passive"))
      (node (ref "Ran12") (pin "2") (pinfunction "2_2") (pintype "passive"))
      (node (ref "Rtan12") (pin "1") (pinfunction "1_1") (pintype "passive"))
    )
    (net (code "10") (name "/AN13") (class "Default")
      (node (ref "J1") (pin "29") (pinfunction "29_29") (pintype "passive"))
      (node (ref "Ran13") (pin "2") (pinfunction "2_2") (pintype "passive"))
      (node (ref "Rtan13") (pin "1") (pinfunction "1_1") (pintype "passive"))
    )
    (net (code "11") (name "/AN14") (class "Default")
      (node (ref "J1") (pin "28") (pinfunction "28_28") (pintype "passive"))
      (node (ref "Ran14") (pin "2") (pinfunction "2_2") (pintype "passive"))
      (node (ref "Rtan14") (pin "1") (pinfunction "1_1") (pintype "passive"))
    )
    (net (code "12") (name "/AN15") (class "Default")
      (node (ref "J1") (pin "27") (pinfunction "27_27") (pintype "passive"))
      (node (ref "Ran15") (pin "2") (pinfunction "2_2") (pintype "passive"))
      (node (ref "Rtan15") (pin "1") (pinfunction "1_1") (pintype "passive"))
    )
    (net (code "13") (name "/BT1") (class "Default")
      (node (ref "BT1") (pin "3") (pinfunction "3_3") (pintype "passive"))
      (node (ref "Rbt1") (pin "2") (pinfunction "2_2") (pintype "passive"))
      (node (ref "Rpbt1") (pin "1") (pinfunction "1_1") (pintype "passive"))
    )
    (net (code "14") (name "/BT2") (class "Default")
      (node (ref "BT2") (pin "3") (pinfunction "3_3") (pintype "passive"))
      (node (ref "Rbt2") (pin "2") (pinfunction "2_2") (pintype "passive"))
      (node (ref "Rpbt2") (pin "1") (pinfunction "1_1") (pintype "passive"))
    )
    (net (code "15") (name "/BT3") (class "Default")
      (node (ref "BT3") (pin "3") (pinfunction "3_3") (pintype "passive"))
      (node (ref "Rbt3") (pin "2") (pinfunction "2_2") (pintype "passive"))
      (node (ref "Rpbt3") (pin "1") (pinfunction "1_1") (pintype "passive"))
    )
    (net (code "16") (name "/BT4") (class "Default")
      (node (ref "BT4") (pin "3") (pinfunction "3_3") (pintype "passive"))
      (node (ref "Rbt4") (pin "2") (pinfunction "2_2") (pintype "passive"))
      (node (ref "Rpbt4") (pin "1") (pinfunction "1_1") (pintype "passive"))
    )
    (net (code "17") (name "/C1RX") (class "Default")
      (node (ref "Ucan") (pin "4") (pinfunction "RXD_4") (pintype "output"))
      (node (ref "Upic") (pin "72") (pinfunction "C1RX/RF0_72") (pintype "bidirectional"))
    )
    (net (code "18") (name "/C1TX") (class "Default")
      (node (ref "Ucan") (pin "1") (pinfunction "TXD_1") (pintype "input"))
      (node (ref "Upic") (pin "73") (pinfunction "C1TX/RF1_73") (pintype "bidirectional"))
    )
    (net (code "19") (name "/CAN_H") (class "Default")
      (node (ref "J1") (pin "3") (pinfunction "3_3") (pintype "passive"))
      (node (ref "Ucan") (pin "7") (pinfunction "CANH_7") (pintype "output"))
    )
    (net (code "20") (name "/CAN_L") (class "Default")
      (node (ref "J1") (pin "4") (pinfunction "4_4") (pintype "passive"))
      (node (ref "Ucan") (pin "6") (pinfunction "CANL_6") (pintype "output"))
    )
    (net (code "21") (name "/IC8") (class "Default")
      (node (ref "Ric8") (pin "2") (pinfunction "2_2") (pintype "passive"))
      (node (ref "Upic") (pin "38") (pinfunction "IC8/CN21/RD15_38") (pintype "bidirectional"))
    )
    (net (code "22") (name "/MCLR") (class "Default")
      (node (ref "J3") (pin "1") (pinfunction "1_1") (pintype "passive"))
      (node (ref "RsMclr") (pin "1") (pinfunction "1_1") (pintype "passive"))
      (node (ref "Upic") (pin "9") (pinfunction "MCLR_9") (pintype "input"))
    )
    (net (code "23") (name "/PGC") (class "Default")
      (node (ref "J3") (pin "5") (pinfunction "5_5") (pintype "passive"))
      (node (ref "Upic") (pin "19") (pinfunction "PGC/EMUC/AN1/CN3/RB1_19") (pintype "bidirectional"))
    )
    (net (code "24") (name "/PGD") (class "Default")
      (node (ref "J3") (pin "4") (pinfunction "4_4") (pintype "passive"))
      (node (ref "Upic") (pin "20") (pinfunction "PGD/EMUD/AN0/CN2/RB0_20") (pintype "bidirectional"))
    )
    (net (code "25") (name "/PWM1H") (class "Default")
      (node (ref "J1") (pin "10") (pinfunction "10_10") (pintype "passive"))
      (node (ref "Upic") (pin "77") (pinfunction "PWM1H/RE1_77") (pintype "bidirectional"))
    )
    (net (code "26") (name "/PWM2H") (class "Default")
      (node (ref "J1") (pin "12") (pinfunction "12_12") (pintype "passive"))
      (node (ref "Upic") (pin "79") (pinfunction "PWM2H/RE3_79") (pintype "bidirectional"))
    )
    (net (code "27") (name "/PWM3H") (class "Default")
      (node (ref "J1") (pin "14") (pinfunction "14_14") (pintype "passive"))
      (node (ref "Upic") (pin "1") (pinfunction "PWM3H/RE5_1") (pintype "bidirectional"))
    )
    (net (code "28") (name "/PWM4H") (class "Default")
      (node (ref "J1") (pin "16") (pinfunction "16_16") (pintype "passive"))
      (node (ref "Upic") (pin "3") (pinfunction "PWM4H/RE7_3") (pintype "bidirectional"))
    )
    (net (code "29") (name "/RA14_INT3") (class "Default")
      (node (ref "J1") (pin "6") (pinfunction "6_6") (pintype "passive"))
      (node (ref "Rint3") (pin "2") (pinfunction "2_2") (pintype "passive"))
      (node (ref "Rtint3") (pin "1") (pinfunction "1_1") (pintype "passive"))
    )
    (net (code "30") (name "/RA15_INT4") (class "Default")
      (node (ref "J1") (pin "5") (pinfunction "5_5") (pintype "passive"))
      (node (ref "Rint4") (pin "2") (pinfunction "2_2") (pintype "passive"))
      (node (ref "Rtint4") (pin "1") (pinfunction "1_1") (pintype "passive"))
    )
    (net (code "31") (name "/RD0") (class "Default")
      (node (ref "J1") (pin "2") (pinfunction "2_2") (pintype "passive"))
      (node (ref "Qrd0") (pin "3") (pinfunction "D_3") (pintype "passive"))
      (node (ref "Ric8") (pin "1") (pinfunction "1_1") (pintype "passive"))
      (node (ref "Rrd0") (pin "2") (pinfunction "2_2") (pintype "passive"))
      (node (ref "Rrd0_o") (pin "2") (pinfunction "2_2") (pintype "passive"))
    )
    (net (code "32") (name "/RE0") (class "Default")
      (node (ref "J1") (pin "9") (pinfunction "9_9") (pintype "passive"))
      (node (ref "Upic") (pin "76") (pinfunction "PWM1L/RE0_76") (pintype "bidirectional"))
    )
    (net (code "33") (name "/RE2") (class "Default")
      (node (ref "J1") (pin "11") (pinfunction "11_11") (pintype "passive"))
      (node (ref "Upic") (pin "78") (pinfunction "PWM2L/RE2_78") (pintype "bidirectional"))
    )
    (net (code "34") (name "/RE4") (class "Default")
      (node (ref "J1") (pin "13") (pinfunction "13_13") (pintype "passive"))
      (node (ref "Upic") (pin "80") (pinfunction "PWM3L/RE4_80") (pintype "bidirectional"))
    )
    (net (code "35") (name "/RE6") (class "Default")
      (node (ref "J1") (pin "15") (pinfunction "15_15") (pintype "passive"))
      (node (ref "Upic") (pin "2") (pinfunction "PWM4L/RE6_2") (pintype "bidirectional"))
    )
    (net (code "36") (name "/RE8_INT1") (class "Default")
      (node (ref "J1") (pin "21") (pinfunction "21_21") (pintype "passive"))
      (node (ref "Rint1") (pin "2") (pinfunction "2_2") (pintype "passive"))
      (node (ref "Rtint1") (pin "1") (pinfunction "1_1") (pintype "passive"))
    )
    (net (code "37") (name "/RE9_INT2") (class "Default")
      (node (ref "J1") (pin "22") (pinfunction "22_22") (pintype "passive"))
      (node (ref "Rint2") (pin "2") (pinfunction "2_2") (pintype "passive"))
      (node (ref "Rtint2") (pin "1") (pinfunction "1_1") (pintype "passive"))
    )
    (net (code "38") (name "/RG0") (class "Default")
      (node (ref "Int1") (pin "COMMON1") (pinfunction "COMMON1_COMMON1") (pintype "passive"))
      (node (ref "Upic") (pin "75") (pinfunction "C2RX/RG0_75") (pintype "bidirectional"))
    )
    (net (code "39") (name "/RG1") (class "Default")
      (node (ref "Int2") (pin "COMMON1") (pinfunction "COMMON1_COMMON1") (pintype "passive"))
      (node (ref "Upic") (pin "74") (pinfunction "C2TX/RG1_74") (pintype "bidirectional"))
    )
    (net (code "40") (name "/RG2_SCL") (class "Default")
      (node (ref "J1") (pin "7") (pinfunction "7_7") (pintype "passive"))
      (node (ref "Rtscl") (pin "1") (pinfunction "1_1") (pintype "passive"))
      (node (ref "Upic") (pin "47") (pinfunction "SCL/RG2_47") (pintype "bidirectional"))
    )
    (net (code "41") (name "/RG3_SDA") (class "Default")
      (node (ref "J1") (pin "8") (pinfunction "8_8") (pintype "passive"))
      (node (ref "Rtsda") (pin "1") (pinfunction "1_1") (pintype "passive"))
      (node (ref "Upic") (pin "46") (pinfunction "SDA/RG3_46") (pintype "bidirectional"))
    )
    (net (code "42") (name "/RG6_SCK2") (class "Default")
      (node (ref "J1") (pin "17") (pinfunction "17_17") (pintype "passive"))
      (node (ref "Upic") (pin "6") (pinfunction "SCK2/CN8/RG6_6") (pintype "bidirectional"))
    )
    (net (code "43") (name "/RG7_SDI2") (class "Default")
      (node (ref "J1") (pin "18") (pinfunction "18_18") (pintype "passive"))
      (node (ref "Upic") (pin "7") (pinfunction "SDI2/CN9/RG7_7") (pintype "bidirectional"))
    )
    (net (code "44") (name "/RG8_SDO2") (class "Default")
      (node (ref "J1") (pin "19") (pinfunction "19_19") (pintype "passive"))
      (node (ref "Upic") (pin "8") (pinfunction "SDO2/CN10/RG8_8") (pintype "bidirectional"))
    )
    (net (code "45") (name "/RG9_SS2") (class "Default")
      (node (ref "J1") (pin "20") (pinfunction "20_20") (pintype "passive"))
      (node (ref "Upic") (pin "10") (pinfunction "SS2/CN11/RG9_10") (pintype "bidirectional"))
    )
    (net (code "46") (name "/U1RX") (class "Default")
      (node (ref "Cu1rx") (pin "2") (pinfunction "2_2") (pintype "passive"))
      (node (ref "Rsu1rx") (pin "2") (pinfunction "2_2") (pintype "passive"))
      (node (ref "Ru1rx") (pin "1") (pinfunction "1_1") (pintype "passive"))
      (node (ref "Upic") (pin "42") (pinfunction "U1RX/RF2_42") (pintype "bidirectional"))
    )
    (net (code "47") (name "/U1TX") (class "Default")
      (node (ref "Rsu1tx") (pin "2") (pinfunction "2_2") (pintype "passive"))
      (node (ref "Upic") (pin "41") (pinfunction "U1TX/RF3_41") (pintype "bidirectional"))
    )
    (net (code "48") (name "/U2RX") (class "Default")
      (node (ref "Cu2rx") (pin "2") (pinfunction "2_2") (pintype "passive"))
      (node (ref "J1") (pin "35") (pinfunction "35_35") (pintype "passive"))
      (node (ref "Ru2rx") (pin "1") (pinfunction "1_1") (pintype "passive"))
      (node (ref "Upic") (pin "39") (pinfunction "U2RX/CN17/RF4_39") (pintype "bidirectional"))
    )
    (net (code "49") (name "/U2TX") (class "Default")
      (node (ref "J1") (pin "36") (pinfunction "36_36") (pintype "passive"))
      (node (ref "Rsu2tx") (pin "1") (pinfunction "1_1") (pintype "passive"))
      (node (ref "Ru2tx") (pin "1") (pinfunction "1_1") (pintype "passive"))
    )
    (net (code "50") (name "/Vref+") (class "Default")
      (node (ref "Cvref1") (pin "2") (pinfunction "2_2") (pintype "passive"))
      (node (ref "Cvref2") (pin "2") (pinfunction "2_2") (pintype "passive"))
      (node (ref "Rvref+") (pin "1") (pinfunction "1_1") (pintype "passive"))
      (node (ref "Upic") (pin "24") (pinfunction "VREF+/RA10_24") (pintype "bidirectional"))
    )
    (net (code "51") (name "/Vref-") (class "Default")
      (node (ref "Rvref-") (pin "2") (pinfunction "2_2") (pintype "passive"))
      (node (ref "Upic") (pin "23") (pinfunction "VREF-/RA9_23") (pintype "bidirectional"))
    )
    (net (code "52") (name "/led1") (class "Default")
      (node (ref "Rled1") (pin "2") (pinfunction "2_2") (pintype "passive"))
      (node (ref "Upic") (pin "54") (pinfunction "IC1/RD8_54") (pintype "bidirectional"))
    )
    (net (code "53") (name "/led2") (class "Default")
      (node (ref "Rled2") (pin "2") (pinfunction "2_2") (pintype "passive"))
      (node (ref "Upic") (pin "55") (pinfunction "IC2/RD9_55") (pintype "bidirectional"))
    )
    (net (code "54") (name "/led3") (class "Default")
      (node (ref "Rled3") (pin "2") (pinfunction "2_2") (pintype "passive"))
      (node (ref "Upic") (pin "56") (pinfunction "IC3/RD10_56") (pintype "bidirectional"))
    )
    (net (code "55") (name "/led4") (class "Default")
      (node (ref "Rled4") (pin "2") (pinfunction "2_2") (pintype "passive"))
      (node (ref "Upic") (pin "57") (pinfunction "IC4/RD11_57") (pintype "bidirectional"))
    )
    (net (code "56") (name "/led5") (class "Default")
      (node (ref "Rled5") (pin "2") (pinfunction "2_2") (pintype "passive"))
      (node (ref "Upic") (pin "64") (pinfunction "IC5/RD12_64") (pintype "bidirectional"))
    )
    (net (code "57") (name "/led6") (class "Default")
      (node (ref "Rled6") (pin "2") (pinfunction "2_2") (pintype "passive"))
      (node (ref "Upic") (pin "65") (pinfunction "IC6/CN19/RD13_65") (pintype "bidirectional"))
    )
    (net (code "58") (name "/pAN2") (class "Default")
      (node (ref "Can2") (pin "2") (pinfunction "2_2") (pintype "passive"))
      (node (ref "Ran2") (pin "1") (pinfunction "1_1") (pintype "passive"))
      (node (ref "Upic") (pin "18") (pinfunction "AN2/SS1/CN4/RB2_18") (pintype "bidirectional"))
    )
    (net (code "59") (name "/pAN3") (class "Default")
      (node (ref "Can3") (pin "2") (pinfunction "2_2") (pintype "passive"))
      (node (ref "Ran3") (pin "1") (pinfunction "1_1") (pintype "passive"))
      (node (ref "Upic") (pin "17") (pinfunction "AN3/INDX/CN5/RB3_17") (pintype "bidirectional"))
    )
    (net (code "60") (name "/pAN4_QEA") (class "Default")
      (node (ref "CqeA") (pin "2") (pinfunction "2_2") (pintype "passive"))
      (node (ref "RqeA") (pin "1") (pinfunction "1_1") (pintype "passive"))
      (node (ref "Upic") (pin "16") (pinfunction "AN4/QEA/CN6/RB4_16") (pintype "bidirectional"))
    )
    (net (code "61") (name "/pAN5_QEB") (class "Default")
      (node (ref "CqeB") (pin "2") (pinfunction "2_2") (pintype "passive"))
      (node (ref "RqeB") (pin "1") (pinfunction "1_1") (pintype "passive"))
      (node (ref "Upic") (pin "15") (pinfunction "AN5/QEB/CN7/RB5_15") (pintype "bidirectional"))
    )
    (net (code "62") (name "/pAN8") (class "Default")
      (node (ref "Can8") (pin "2") (pinfunction "2_2") (pintype "passive"))
      (node (ref "Ran8") (pin "1") (pinfunction "1_1") (pintype "passive"))
      (node (ref "Upic") (pin "27") (pinfunction "AN8/RB8_27") (pintype "bidirectional"))
    )
    (net (code "63") (name "/pAN9") (class "Default")
      (node (ref "Can9") (pin "2") (pinfunction "2_2") (pintype "passive"))
      (node (ref "Ran9") (pin "1") (pinfunction "1_1") (pintype "passive"))
      (node (ref "Upic") (pin "28") (pinfunction "AN9/RB9_28") (pintype "bidirectional"))
    )
    (net (code "64") (name "/pAN10") (class "Default")
      (node (ref "Can10") (pin "2") (pinfunction "2_2") (pintype "passive"))
      (node (ref "Ran10") (pin "1") (pinfunction "1_1") (pintype "passive"))
      (node (ref "Upic") (pin "29") (pinfunction "AN10/RB10_29") (pintype "bidirectional"))
    )
    (net (code "65") (name "/pAN11") (class "Default")
      (node (ref "Can11") (pin "2") (pinfunction "2_2") (pintype "passive"))
      (node (ref "Ran11") (pin "1") (pinfunction "1_1") (pintype "passive"))
      (node (ref "Upic") (pin "30") (pinfunction "AN11/RB11_30") (pintype "bidirectional"))
    )
    (net (code "66") (name "/pAN12") (class "Default")
      (node (ref "Can12") (pin "2") (pinfunction "2_2") (pintype "passive"))
      (node (ref "Ran12") (pin "1") (pinfunction "1_1") (pintype "passive"))
      (node (ref "Upic") (pin "33") (pinfunction "AN12/RB12_33") (pintype "bidirectional"))
    )
    (net (code "67") (name "/pAN13") (class "Default")
      (node (ref "Can13") (pin "2") (pinfunction "2_2") (pintype "passive"))
      (node (ref "Ran13") (pin "1") (pinfunction "1_1") (pintype "passive"))
      (node (ref "Upic") (pin "34") (pinfunction "AN13/RB13_34") (pintype "bidirectional"))
    )
    (net (code "68") (name "/pAN14") (class "Default")
      (node (ref "Can14") (pin "2") (pinfunction "2_2") (pintype "passive"))
      (node (ref "Ran14") (pin "1") (pinfunction "1_1") (pintype "passive"))
      (node (ref "Upic") (pin "35") (pinfunction "AN14/RB14_35") (pintype "bidirectional"))
    )
    (net (code "69") (name "/pAN15") (class "Default")
      (node (ref "Can15") (pin "2") (pinfunction "2_2") (pintype "passive"))
      (node (ref "Ran15") (pin "1") (pinfunction "1_1") (pintype "passive"))
      (node (ref "Upic") (pin "36") (pinfunction "AN15/OCFB/CN12/RB15_36") (pintype "bidirectional"))
    )
    (net (code "70") (name "/pBT1") (class "Default")
      (node (ref "Cbt1") (pin "2") (pinfunction "2_2") (pintype "passive"))
      (node (ref "Rbt1") (pin "1") (pinfunction "1_1") (pintype "passive"))
      (node (ref "Upic") (pin "66") (pinfunction "OC5/CN13/RD4_66") (pintype "bidirectional"))
    )
    (net (code "71") (name "/pBT2") (class "Default")
      (node (ref "Cbt2") (pin "2") (pinfunction "2_2") (pintype "passive"))
      (node (ref "Rbt2") (pin "1") (pinfunction "1_1") (pintype "passive"))
      (node (ref "Upic") (pin "67") (pinfunction "OC6/CN14/RD5_67") (pintype "bidirectional"))
    )
    (net (code "72") (name "/pBT3") (class "Default")
      (node (ref "Cbt3") (pin "2") (pinfunction "2_2") (pintype "passive"))
      (node (ref "Rbt3") (pin "1") (pinfunction "1_1") (pintype "passive"))
      (node (ref "Upic") (pin "68") (pinfunction "OC7/CN15/RD6_68") (pintype "bidirectional"))
    )
    (net (code "73") (name "/pBT4") (class "Default")
      (node (ref "Cbt4") (pin "2") (pinfunction "2_2") (pintype "passive"))
      (node (ref "Rbt4") (pin "1") (pinfunction "1_1") (pintype "passive"))
      (node (ref "Upic") (pin "69") (pinfunction "OC8/UPDN/CN16/RD7_69") (pintype "bidirectional"))
    )
    (net (code "74") (name "/pRA14_INT3") (class "Default")
      (node (ref "Cint3") (pin "2") (pinfunction "2_2") (pintype "passive"))
      (node (ref "Rint3") (pin "1") (pinfunction "1_1") (pintype "passive"))
      (node (ref "Upic") (pin "52") (pinfunction "INT3/RA14_52") (pintype "bidirectional"))
    )
    (net (code "75") (name "/pRA15_INT4") (class "Default")
      (node (ref "Cint4") (pin "2") (pinfunction "2_2") (pintype "passive"))
      (node (ref "Rint4") (pin "1") (pinfunction "1_1") (pintype "passive"))
      (node (ref "Upic") (pin "53") (pinfunction "INT4/RA15_53") (pintype "bidirectional"))
    )
    (net (code "76") (name "/pRD0") (class "Default")
      (node (ref "Crd0") (pin "2") (pinfunction "2_2") (pintype "passive"))
      (node (ref "Qrd0") (pin "1") (pinfunction "G_1") (pintype "passive"))
      (node (ref "Rrd0") (pin "1") (pinfunction "1_1") (pintype "passive"))
      (node (ref "Rrd0_o") (pin "1") (pinfunction "1_1") (pintype "passive"))
      (node (ref "Upic") (pin "58") (pinfunction "EMUC2/OC1/RD0_58") (pintype "bidirectional"))
    )
    (net (code "77") (name "/pRE8_INT1") (class "Default")
      (node (ref "Cint1") (pin "2") (pinfunction "2_2") (pintype "passive"))
      (node (ref "Rint1") (pin "1") (pinfunction "1_1") (pintype "passive"))
      (node (ref "Upic") (pin "13") (pinfunction "FLTA/INT1/RE8_13") (pintype "bidirectional"))
    )
    (net (code "78") (name "/pRE9_INT2") (class "Default")
      (node (ref "Cint2") (pin "2") (pinfunction "2_2") (pintype "passive"))
      (node (ref "Rint2") (pin "1") (pinfunction "1_1") (pintype "passive"))
      (node (ref "Upic") (pin "14") (pinfunction "FLTB/INT2/RE9_14") (pintype "bidirectional"))
    )
    (net (code "79") (name "/pU2TX") (class "Default")
      (node (ref "Rsu2tx") (pin "2") (pinfunction "2_2") (pintype "passive"))
      (node (ref "Upic") (pin "40") (pinfunction "U2TX/CN18/RF5_40") (pintype "bidirectional"))
    )
    (net (code "80") (name "GND") (class "Default")
      (node (ref "B1") (pin "2") (pinfunction "B2_2") (pintype "passive"))
      (node (ref "BT1") (pin "1") (pinfunction "1_1") (pintype "passive"))
      (node (ref "BT2") (pin "1") (pinfunction "1_1") (pintype "passive"))
      (node (ref "BT3") (pin "1") (pinfunction "1_1") (pintype "passive"))
      (node (ref "BT4") (pin "1") (pinfunction "1_1") (pintype "passive"))
      (node (ref "Can10") (pin "1") (pinfunction "1_1") (pintype "passive"))
      (node (ref "Can11") (pin "1") (pinfunction "1_1") (pintype "passive"))
      (node (ref "Can12") (pin "1") (pinfunction "1_1") (pintype "passive"))
      (node (ref "Can13") (pin "1") (pinfunction "1_1") (pintype "passive"))
      (node (ref "Can14") (pin "1") (pinfunction "1_1") (pintype "passive"))
      (node (ref "Can15") (pin "1") (pinfunction "1_1") (pintype "passive"))
      (node (ref "Can2") (pin "1") (pinfunction "1_1") (pintype "passive"))
      (node (ref "Can3") (pin "1") (pinfunction "1_1") (pintype "passive"))
      (node (ref "Can8") (pin "1") (pinfunction "1_1") (pintype "passive"))
      (node (ref "Can9") (pin "1") (pinfunction "1_1") (pintype "passive"))
      (node (ref "Cbt1") (pin "1") (pinfunction "1_1") (pintype "passive"))
      (node (ref "Cbt2") (pin "1") (pinfunction "1_1") (pintype "passive"))
      (node (ref "Cbt3") (pin "1") (pinfunction "1_1") (pintype "passive"))
      (node (ref "Cbt4") (pin "1") (pinfunction "1_1") (pintype "passive"))
      (node (ref "Cdcan1") (pin "1") (pinfunction "1_1") (pintype "passive"))
      (node (ref "Cdcan2") (pin "1") (pinfunction "1_1") (pintype "passive"))
      (node (ref "Cdpic1") (pin "2") (pinfunction "2_2") (pintype "passive"))
      (node (ref "Cdpic2") (pin "2") (pinfunction "2_2") (pintype "passive"))
      (node (ref "Cdpic3") (pin "2") (pinfunction "2_2") (pintype "passive"))
      (node (ref "Cdpic4") (pin "2") (pinfunction "2_2") (pintype "passive"))
      (node (ref "Cin") (pin "1") (pinfunction "1_1") (pintype "passive"))
      (node (ref "Cin2") (pin "1") (pinfunction "1_1") (pintype "passive"))
      (node (ref "Cint1") (pin "1") (pinfunction "1_1") (pintype "passive"))
      (node (ref "Cint2") (pin "1") (pinfunction "1_1") (pintype "passive"))
      (node (ref "Cint3") (pin "1") (pinfunction "1_1") (pintype "passive"))
      (node (ref "Cint4") (pin "1") (pinfunction "1_1") (pintype "passive"))
      (node (ref "Cmclr") (pin "1") (pinfunction "1_1") (pintype "passive"))
      (node (ref "Cout") (pin "1") (pinfunction "1_1") (pintype "passive"))
      (node (ref "Cout2") (pin "1") (pinfunction "1_1") (pintype "passive"))
      (node (ref "Cq1") (pin "2") (pinfunction "2_2") (pintype "passive"))
      (node (ref "Cq2") (pin "2") (pinfunction "2_2") (pintype "passive"))
      (node (ref "CqeA") (pin "1") (pinfunction "1_1") (pintype "passive"))
      (node (ref "CqeB") (pin "1") (pinfunction "1_1") (pintype "passive"))
      (node (ref "Crd0") (pin "1") (pinfunction "1_1") (pintype "passive"))
      (node (ref "Cu1rx") (pin "1") (pinfunction "1_1") (pintype "passive"))
      (node (ref "Cu2rx") (pin "1") (pinfunction "1_1") (pintype "passive"))
      (node (ref "Cvref1") (pin "1") (pinfunction "1_1") (pintype "passive"))
      (node (ref "Cvref2") (pin "1") (pinfunction "1_1") (pintype "passive"))
      (node (ref "D1") (pin "2") (pinfunction "2_2") (pintype "passive"))
      (node (ref "D2") (pin "2") (pinfunction "2_2") (pintype "passive"))
      (node (ref "D3") (pin "2") (pinfunction "2_2") (pintype "passive"))
      (node (ref "D4") (pin "2") (pinfunction "2_2") (pintype "passive"))
      (node (ref "D5") (pin "2") (pinfunction "2_2") (pintype "passive"))
      (node (ref "D6") (pin "2") (pinfunction "2_2") (pintype "passive"))
      (node (ref "Int1") (pin "NC1") (pinfunction "NC1_NC1") (pintype "passive"))
      (node (ref "Int2") (pin "NC1") (pinfunction "NC1_NC1") (pintype "passive"))
      (node (ref "J1") (pin "1") (pinfunction "1_1") (pintype "passive"))
      (node (ref "J1") (pin "38") (pinfunction "38_38") (pintype "passive"))
      (node (ref "J1") (pin "39") (pinfunction "39_39") (pintype "passive"))
      (node (ref "J3") (pin "3") (pinfunction "3_3") (pintype "passive"))
      (node (ref "J3") (pin "FIX1") (pinfunction "FIX1_FIX1") (pintype "passive"))
      (node (ref "J3") (pin "FIX2") (pinfunction "FIX2_FIX2") (pintype "passive"))
      (node (ref "J6") (pin "5") (pinfunction "5_5") (pintype "passive"))
      (node (ref "J6") (pin "6") (pinfunction "6_6") (pintype "passive"))
      (node (ref "J6") (pin "FIX1") (pinfunction "FIX1_FIX1") (pintype "passive"))
      (node (ref "J6") (pin "FIX2") (pinfunction "FIX2_FIX2") (pintype "passive"))
      (node (ref "Qrd0") (pin "2") (pinfunction "S_2") (pintype "passive"))
      (node (ref "Rvref-") (pin "1") (pinfunction "1_1") (pintype "passive"))
      (node (ref "SW1") (pin "1") (pinfunction "1_1") (pintype "passive"))
      (node (ref "Ucan") (pin "2") (pinfunction "GND_2") (pintype "power_in"))
      (node (ref "Ucan") (pin "8") (pinfunction "RS_8") (pintype "passive"))
      (node (ref "Upic") (pin "11") (pinfunction "VSS_11") (pintype "power_in"))
      (node (ref "Upic") (pin "26") (pinfunction "AVSS_26") (pintype "power_in"))
      (node (ref "Upic") (pin "31") (pinfunction "VSS_31") (pintype "power_in"))
      (node (ref "Upic") (pin "51") (pinfunction "VSS_51") (pintype "power_in"))
      (node (ref "Upic") (pin "70") (pinfunction "VSS_70") (pintype "power_in"))
      (node (ref "Ureg") (pin "4") (pinfunction "GND_4") (pintype "power_in"))
      (node (ref "Vis1") (pin "1") (pinfunction "1_1") (pintype "passive"))
      (node (ref "Vis2") (pin "1") (pinfunction "1_1") (pintype "passive"))
    )
    (net (code "81") (name "Net-(Cmclr-Pad2)") (class "Default")
      (node (ref "Cmclr") (pin "2") (pinfunction "2_2") (pintype "passive"))
      (node (ref "Rmclr") (pin "1") (pinfunction "1_1") (pintype "passive"))
      (node (ref "RsMclr") (pin "2") (pinfunction "2_2") (pintype "passive"))
      (node (ref "SW1") (pin "3") (pinfunction "3_3") (pintype "passive"))
    )
    (net (code "82") (name "Net-(D1-Pad1)") (class "Default")
      (node (ref "D1") (pin "1") (pinfunction "1_1") (pintype "passive"))
      (node (ref "Rled1") (pin "1") (pinfunction "1_1") (pintype "passive"))
    )
    (net (code "83") (name "Net-(D2-Pad1)") (class "Default")
      (node (ref "D2") (pin "1") (pinfunction "1_1") (pintype "passive"))
      (node (ref "Rled2") (pin "1") (pinfunction "1_1") (pintype "passive"))
    )
    (net (code "84") (name "Net-(D3-Pad1)") (class "Default")
      (node (ref "D3") (pin "1") (pinfunction "1_1") (pintype "passive"))
      (node (ref "Rled3") (pin "1") (pinfunction "1_1") (pintype "passive"))
    )
    (net (code "85") (name "Net-(D4-Pad1)") (class "Default")
      (node (ref "D4") (pin "1") (pinfunction "1_1") (pintype "passive"))
      (node (ref "Rled4") (pin "1") (pinfunction "1_1") (pintype "passive"))
    )
    (net (code "86") (name "Net-(D5-Pad1)") (class "Default")
      (node (ref "D5") (pin "1") (pinfunction "1_1") (pintype "passive"))
      (node (ref "Rled5") (pin "1") (pinfunction "1_1") (pintype "passive"))
    )
    (net (code "87") (name "Net-(D6-Pad1)") (class "Default")
      (node (ref "D6") (pin "1") (pinfunction "1_1") (pintype "passive"))
      (node (ref "Rled6") (pin "1") (pinfunction "1_1") (pintype "passive"))
    )
    (net (code "88") (name "Net-(J6-Pad3)") (class "Default")
      (node (ref "J6") (pin "3") (pinfunction "3_3") (pintype "passive"))
      (node (ref "Rsu1tx") (pin "1") (pinfunction "1_1") (pintype "passive"))
      (node (ref "Ru1tx") (pin "1") (pinfunction "1_1") (pintype "passive"))
    )
    (net (code "89") (name "Net-(J6-Pad4)") (class "Default")
      (node (ref "J6") (pin "4") (pinfunction "4_4") (pintype "passive"))
      (node (ref "Rsu1rx") (pin "1") (pinfunction "1_1") (pintype "passive"))
    )
    (net (code "90") (name "Net-(Q-OSC1)") (class "Default")
      (node (ref "Cq2") (pin "1") (pinfunction "1_1") (pintype "passive"))
      (node (ref "Q") (pin "1") (pinfunction "OSC1_1") (pintype "passive"))
      (node (ref "Upic") (pin "49") (pinfunction "OSC1/CLKI_49") (pintype "input"))
    )
    (net (code "91") (name "Net-(Q-OSC2)") (class "Default")
      (node (ref "Cq1") (pin "1") (pinfunction "1_1") (pintype "passive"))
      (node (ref "Q") (pin "2") (pinfunction "OSC2_2") (pintype "passive"))
      (node (ref "Upic") (pin "50") (pinfunction "OSC2/CLKO/RC15_50") (pintype "bidirectional"))
    )
    (net (code "92") (name "VCC") (class "Default")
      (node (ref "B1") (pin "1") (pinfunction "B1_1") (pintype "passive"))
      (node (ref "Cin") (pin "2") (pinfunction "2_2") (pintype "passive"))
      (node (ref "Cin2") (pin "2") (pinfunction "2_2") (pintype "passive"))
      (node (ref "J1") (pin "40") (pinfunction "40_40") (pintype "passive"))
      (node (ref "Ureg") (pin "1") (pinfunction "IN_1") (pintype "power_in"))
    )
    (net (code "93") (name "Vdd") (class "Default")
      (node (ref "Cdcan1") (pin "2") (pinfunction "2_2") (pintype "passive"))
      (node (ref "Cdcan2") (pin "2") (pinfunction "2_2") (pintype "passive"))
      (node (ref "Cdpic1") (pin "1") (pinfunction "1_1") (pintype "passive"))
      (node (ref "Cdpic2") (pin "1") (pinfunction "1_1") (pintype "passive"))
      (node (ref "Cdpic3") (pin "1") (pinfunction "1_1") (pintype "passive"))
      (node (ref "Cdpic4") (pin "1") (pinfunction "1_1") (pintype "passive"))
      (node (ref "Cout") (pin "2") (pinfunction "2_2") (pintype "passive"))
      (node (ref "Cout2") (pin "2") (pinfunction "2_2") (pintype "passive"))
      (node (ref "Int1") (pin "NO1") (pinfunction "NO1_NO1") (pintype "passive"))
      (node (ref "Int2") (pin "NO1") (pinfunction "NO1_NO1") (pintype "passive"))
      (node (ref "J1") (pin "37") (pinfunction "37_37") (pintype "passive"))
      (node (ref "J3") (pin "2") (pinfunction "2_2") (pintype "passive"))
      (node (ref "J6") (pin "1") (pinfunction "1_1") (pintype "passive"))
      (node (ref "J6") (pin "2") (pinfunction "2_2") (pintype "passive"))
      (node (ref "Rmclr") (pin "2") (pinfunction "2_2") (pintype "passive"))
      (node (ref "Rpbt1") (pin "2") (pinfunction "2_2") (pintype "passive"))
      (node (ref "Rpbt2") (pin "2") (pinfunction "2_2") (pintype "passive"))
      (node (ref "Rpbt3") (pin "2") (pinfunction "2_2") (pintype "passive"))
      (node (ref "Rpbt4") (pin "2") (pinfunction "2_2") (pintype "passive"))
      (node (ref "Rtan10") (pin "2") (pinfunction "2_2") (pintype "passive"))
      (node (ref "Rtan11") (pin "2") (pinfunction "2_2") (pintype "passive"))
      (node (ref "Rtan12") (pin "2") (pinfunction "2_2") (pintype "passive"))
      (node (ref "Rtan13") (pin "2") (pinfunction "2_2") (pintype "passive"))
      (node (ref "Rtan14") (pin "2") (pinfunction "2_2") (pintype "passive"))
      (node (ref "Rtan15") (pin "2") (pinfunction "2_2") (pintype "passive"))
      (node (ref "Rtan2") (pin "2") (pinfunction "2_2") (pintype "passive"))
      (node (ref "Rtan3") (pin "2") (pinfunction "2_2") (pintype "passive"))
      (node (ref "Rtan8") (pin "2") (pinfunction "2_2") (pintype "passive"))
      (node (ref "Rtan9") (pin "2") (pinfunction "2_2") (pintype "passive"))
      (node (ref "Rtint1") (pin "2") (pinfunction "2_2") (pintype "passive"))
      (node (ref "Rtint2") (pin "2") (pinfunction "2_2") (pintype "passive"))
      (node (ref "Rtint3") (pin "2") (pinfunction "2_2") (pintype "passive"))
      (node (ref "Rtint4") (pin "2") (pinfunction "2_2") (pintype "passive"))
      (node (ref "RtqeA") (pin "2") (pinfunction "2_2") (pintype "passive"))
      (node (ref "RtqeB") (pin "2") (pinfunction "2_2") (pintype "passive"))
      (node (ref "Rtscl") (pin "2") (pinfunction "2_2") (pintype "passive"))
      (node (ref "Rtsda") (pin "2") (pinfunction "2_2") (pintype "passive"))
      (node (ref "Ru1rx") (pin "2") (pinfunction "2_2") (pintype "passive"))
      (node (ref "Ru1tx") (pin "2") (pinfunction "2_2") (pintype "passive"))
      (node (ref "Ru2rx") (pin "2") (pinfunction "2_2") (pintype "passive"))
      (node (ref "Ru2tx") (pin "2") (pinfunction "2_2") (pintype "passive"))
      (node (ref "Rvref+") (pin "2") (pinfunction "2_2") (pintype "passive"))
      (node (ref "Ucan") (pin "3") (pinfunction "VDD_3") (pintype "power_in"))
      (node (ref "Upic") (pin "12") (pinfunction "VDD_12") (pintype "power_in"))
      (node (ref "Upic") (pin "25") (pinfunction "AVDD_25") (pintype "power_in"))
      (node (ref "Upic") (pin "32") (pinfunction "VDD_32") (pintype "power_in"))
      (node (ref "Upic") (pin "48") (pinfunction "VDD_48") (pintype "power_in"))
      (node (ref "Upic") (pin "71") (pinfunction "VDD_71") (pintype "power_in"))
      (node (ref "Ureg") (pin "3") (pinfunction "OUT_3") (pintype "power_in"))
    )
    (net (code "94") (name "unconnected-(J3-Pad6)") (class "Default")
      (node (ref "J3") (pin "6") (pinfunction "6_6") (pintype "passive"))
    )
    (net (code "95") (name "unconnected-(Ucan-VREF-Pad5)") (class "Default")
      (node (ref "Ucan") (pin "5") (pinfunction "VREF_5") (pintype "output"))
    )
    (net (code "96") (name "unconnected-(Upic-AN6{slash}OCFA{slash}RB6-Pad21)") (class "Default")
      (node (ref "Upic") (pin "21") (pinfunction "AN6/OCFA/RB6_21") (pintype "bidirectional+no_connect"))
    )
    (net (code "97") (name "unconnected-(Upic-AN7{slash}RB7-Pad22)") (class "Default")
      (node (ref "Upic") (pin "22") (pinfunction "AN7/RB7_22") (pintype "bidirectional+no_connect"))
    )
    (net (code "98") (name "unconnected-(Upic-EMUC1{slash}SOSCO{slash}T1CK{slash}CN0{slash}RC14-Pad60)") (class "Default")
      (node (ref "Upic") (pin "60") (pinfunction "EMUC1/SOSCO/T1CK/CN0/RC14_60") (pintype "bidirectional+no_connect"))
    )
    (net (code "99") (name "unconnected-(Upic-EMUC3{slash}SCK1{slash}INT0{slash}RF6-Pad45)") (class "Default")
      (node (ref "Upic") (pin "45") (pinfunction "EMUC3/SCK1/INT0/RF6_45") (pintype "bidirectional+no_connect"))
    )
    (net (code "100") (name "unconnected-(Upic-EMUD1{slash}SOSCI{slash}CN1{slash}RC13-Pad59)") (class "Default")
      (node (ref "Upic") (pin "59") (pinfunction "EMUD1/SOSCI/CN1/RC13_59") (pintype "bidirectional+no_connect"))
    )
    (net (code "101") (name "unconnected-(Upic-EMUD2{slash}OC2{slash}RD1-Pad61)") (class "Default")
      (node (ref "Upic") (pin "61") (pinfunction "EMUD2/OC2/RD1_61") (pintype "bidirectional+no_connect"))
    )
    (net (code "102") (name "unconnected-(Upic-EMUD3{slash}SDO1{slash}RF8-Pad43)") (class "Default")
      (node (ref "Upic") (pin "43") (pinfunction "EMUD3/SDO1/RF8_43") (pintype "bidirectional+no_connect"))
    )
    (net (code "103") (name "unconnected-(Upic-IC7{slash}CN20{slash}RD14-Pad37)") (class "Default")
      (node (ref "Upic") (pin "37") (pinfunction "IC7/CN20/RD14_37") (pintype "bidirectional+no_connect"))
    )
    (net (code "104") (name "unconnected-(Upic-OC3{slash}RD2-Pad62)") (class "Default")
      (node (ref "Upic") (pin "62") (pinfunction "OC3/RD2_62") (pintype "bidirectional+no_connect"))
    )
    (net (code "105") (name "unconnected-(Upic-OC4{slash}RD3-Pad63)") (class "Default")
      (node (ref "Upic") (pin "63") (pinfunction "OC4/RD3_63") (pintype "bidirectional+no_connect"))
    )
    (net (code "106") (name "unconnected-(Upic-SDI1{slash}RF7-Pad44)") (class "Default")
      (node (ref "Upic") (pin "44") (pinfunction "SDI1/RF7_44") (pintype "bidirectional+no_connect"))
    )
    (net (code "107") (name "unconnected-(Upic-T2CK{slash}RC1-Pad4)") (class "Default")
      (node (ref "Upic") (pin "4") (pinfunction "T2CK/RC1_4") (pintype "bidirectional+no_connect"))
    )
    (net (code "108") (name "unconnected-(Upic-T4CK{slash}RC3-Pad5)") (class "Default")
      (node (ref "Upic") (pin "5") (pinfunction "T4CK/RC3_5") (pintype "bidirectional+no_connect"))
    )
  )
)
